# latch_THT_v2.net
KiCad netlist of a schematic drawn in EAGLE
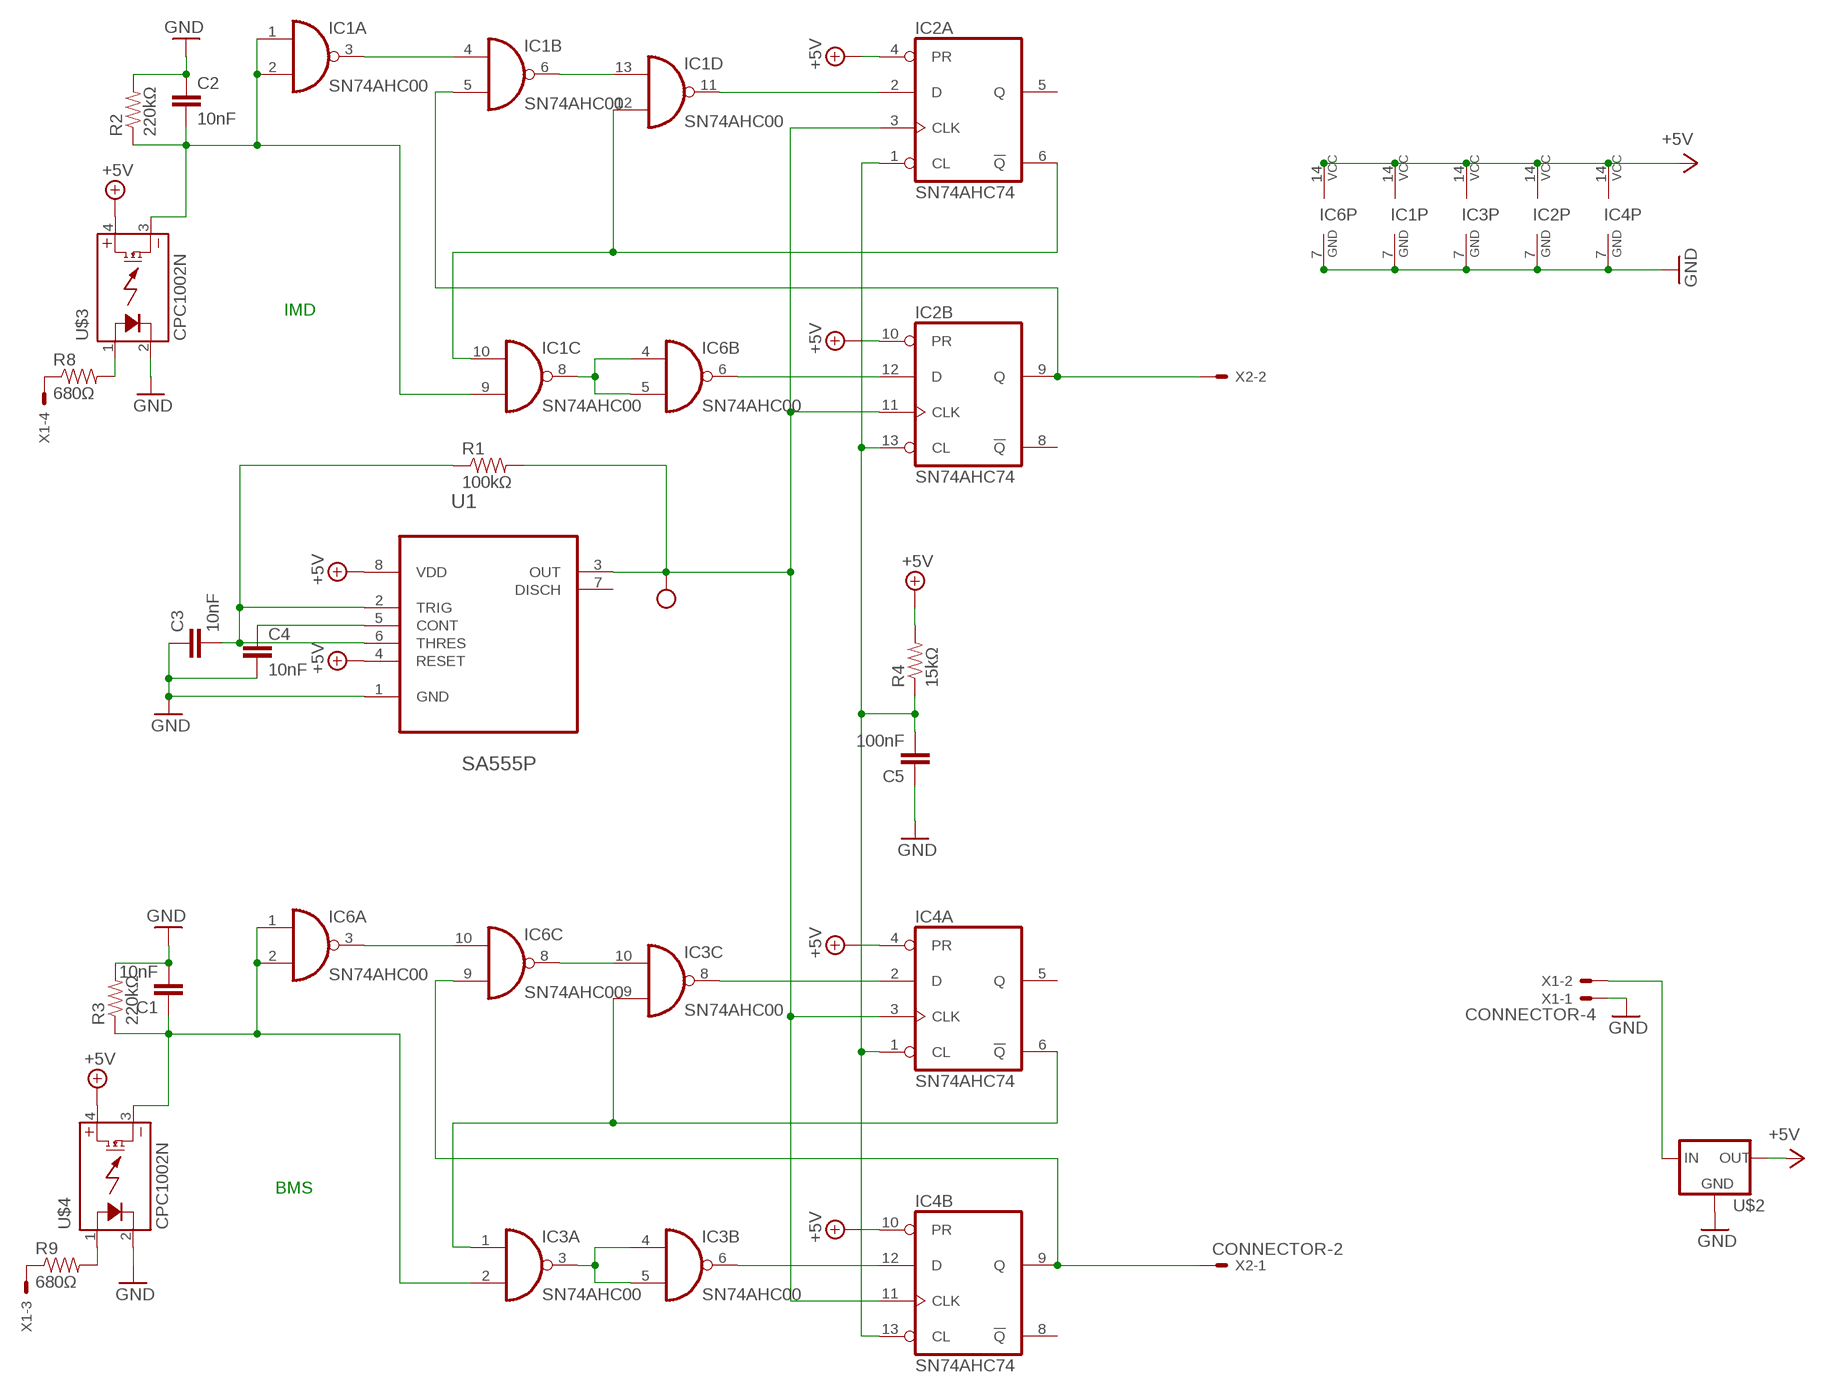
[diagram p0: schematic, sheet 1]

(export (version "E")
  (design (tool "Eeschema 10.0.6"))
  (components
    (comp (ref "C1")
      (value "10nF")
      (footprint "eagle-import:AXIAL-5MM")
      (libsource (lib "eagle-import") (part "CAP_"))
    )
    (comp (ref "C2")
      (value "10nF")
      (footprint "eagle-import:AXIAL-5MM")
      (libsource (lib "eagle-import") (part "CAP_"))
    )
    (comp (ref "C3")
      (value "10nF")
      (footprint "eagle-import:AXIAL-5MM")
      (libsource (lib "eagle-import") (part "CAP_"))
    )
    (comp (ref "C4")
      (value "10nF")
      (footprint "eagle-import:AXIAL-5MM")
      (libsource (lib "eagle-import") (part "CAP_"))
    )
    (comp (ref "C5")
      (value "100nF")
      (footprint "eagle-import:AXIAL-5MM")
      (libsource (lib "eagle-import") (part "CAP_"))
    )
    (comp (ref "IC1")
      (value "SN74AHC00")
      (footprint "eagle-import:DIL14")
      (libsource (lib "eagle-import") (part "SN74AHC00"))
    )
    (comp (ref "IC2")
      (value "SN74AHC74")
      (footprint "eagle-import:DIL14")
      (libsource (lib "eagle-import") (part "SN74AHC74"))
    )
    (comp (ref "IC3")
      (value "SN74AHC00")
      (footprint "eagle-import:DIL14")
      (libsource (lib "eagle-import") (part "SN74AHC00"))
    )
    (comp (ref "IC4")
      (value "SN74AHC74")
      (footprint "eagle-import:DIL14")
      (libsource (lib "eagle-import") (part "SN74AHC74"))
    )
    (comp (ref "IC6")
      (value "SN74AHC00")
      (footprint "eagle-import:DIL14")
      (libsource (lib "eagle-import") (part "SN74AHC00"))
    )
    (comp (ref "R1")
      (value "100kΩ")
      (footprint "eagle-import:AXIAL-0.4")
      (libsource (lib "eagle-import") (part "RESISTORPTH-1/4W"))
    )
    (comp (ref "R2")
      (value "220kΩ")
      (footprint "eagle-import:AXIAL-0.4")
      (libsource (lib "eagle-import") (part "RESISTORPTH-1/4W"))
    )
    (comp (ref "R3")
      (value "220kΩ")
      (footprint "eagle-import:AXIAL-0.4")
      (libsource (lib "eagle-import") (part "RESISTORPTH-1/4W"))
    )
    (comp (ref "R4")
      (value "15kΩ")
      (footprint "eagle-import:AXIAL-0.4")
      (libsource (lib "eagle-import") (part "RESISTORPTH-1/4W"))
    )
    (comp (ref "R8")
      (value "680Ω")
      (footprint "eagle-import:AXIAL-0.4")
      (libsource (lib "eagle-import") (part "RESISTORPTH-1/4W"))
    )
    (comp (ref "R9")
      (value "680Ω")
      (footprint "eagle-import:AXIAL-0.4")
      (libsource (lib "eagle-import") (part "RESISTORPTH-1/4W"))
    )
    (comp (ref "U$1")
      (value "TEST_POINT")
      (footprint "eagle-import:TEST_POINT")
      (libsource (lib "eagle-import") (part "TEST_POINT"))
    )
    (comp (ref "U$2")
      (value "5VREG_LM340-NLM340T-5.0/NOPB")
      (footprint "eagle-import:TO-220")
      (libsource (lib "eagle-import") (part "5VREG_LM340-NLM340T-5.0/NOPB"))
    )
    (comp (ref "U$3")
      (value "CPC1002N")
      (footprint "eagle-import:SOP04")
      (libsource (lib "eagle-import") (part "CPC1002N"))
    )
    (comp (ref "U$4")
      (value "CPC1002N")
      (footprint "eagle-import:SOP04")
      (libsource (lib "eagle-import") (part "CPC1002N"))
    )
    (comp (ref "U1")
      (value "SA555P")
      (footprint "eagle-import:DIP254P762X508-8")
      (libsource (lib "eagle-import") (part "SA555P"))
    )
    (comp (ref "X1")
      (value "CONNECTOR-4")
      (footprint "eagle-import:MINIFIT_5566-4")
      (libsource (lib "eagle-import") (part "CONNECTOR-4"))
    )
    (comp (ref "X2")
      (value "CONNECTOR-2")
      (footprint "eagle-import:MINIFIT_5566-2")
      (libsource (lib "eagle-import") (part "CONNECTOR-2"))
    )
  )
  (nets
    (net (code "1") (name "+5V") (class "Default")
      (node (ref "IC1") (pin "14") (pinfunction "VCC_14") (pintype "power_in"))
      (node (ref "IC2") (pin "10") (pinfunction "PR_10") (pintype "input"))
      (node (ref "IC2") (pin "14") (pinfunction "VCC_14") (pintype "power_in"))
      (node (ref "IC2") (pin "4") (pinfunction "PR_4") (pintype "input"))
      (node (ref "IC3") (pin "14") (pinfunction "VCC_14") (pintype "power_in"))
      (node (ref "IC4") (pin "10") (pinfunction "PR_10") (pintype "input"))
      (node (ref "IC4") (pin "14") (pinfunction "VCC_14") (pintype "power_in"))
      (node (ref "IC4") (pin "4") (pinfunction "PR_4") (pintype "input"))
      (node (ref "IC6") (pin "14") (pinfunction "VCC_14") (pintype "power_in"))
      (node (ref "R4") (pin "P$2") (pinfunction "2_P$2") (pintype "passive"))
      (node (ref "U$2") (pin "3") (pinfunction "OUT_3") (pintype "output"))
      (node (ref "U$3") (pin "4") (pinfunction "DC+_4") (pintype "passive"))
      (node (ref "U$4") (pin "4") (pinfunction "DC+_4") (pintype "passive"))
      (node (ref "U1") (pin "4") (pinfunction "RESET_4") (pintype "input"))
      (node (ref "U1") (pin "8") (pinfunction "VDD_8") (pintype "power_in"))
    )
    (net (code "2") (name "GND") (class "Default")
      (node (ref "C1") (pin "P$2") (pinfunction "2_P$2") (pintype "passive"))
      (node (ref "C2") (pin "P$1") (pinfunction "1_P$1") (pintype "passive"))
      (node (ref "C3") (pin "P$1") (pinfunction "1_P$1") (pintype "passive"))
      (node (ref "C4") (pin "P$2") (pinfunction "2_P$2") (pintype "passive"))
      (node (ref "C5") (pin "P$1") (pinfunction "1_P$1") (pintype "passive"))
      (node (ref "IC1") (pin "7") (pinfunction "GND_7") (pintype "power_in"))
      (node (ref "IC2") (pin "7") (pinfunction "GND_7") (pintype "power_in"))
      (node (ref "IC3") (pin "7") (pinfunction "GND_7") (pintype "power_in"))
      (node (ref "IC4") (pin "7") (pinfunction "GND_7") (pintype "power_in"))
      (node (ref "IC6") (pin "7") (pinfunction "GND_7") (pintype "power_in"))
      (node (ref "R2") (pin "P$2") (pinfunction "2_P$2") (pintype "passive"))
      (node (ref "R3") (pin "P$2") (pinfunction "2_P$2") (pintype "passive"))
      (node (ref "U$2") (pin "2") (pinfunction "GND_2") (pintype "input"))
      (node (ref "U$3") (pin "2") (pinfunction "CONTROL-_2") (pintype "passive"))
      (node (ref "U$4") (pin "2") (pinfunction "CONTROL-_2") (pintype "passive"))
      (node (ref "U1") (pin "1") (pinfunction "GND_1") (pintype "passive"))
      (node (ref "X1") (pin "1") (pinfunction "S_1") (pintype "passive"))
    )
    (net (code "3") (name "Net-(C1-1)") (class "Default")
      (node (ref "C1") (pin "P$1") (pinfunction "1_P$1") (pintype "passive"))
      (node (ref "IC3") (pin "2") (pinfunction "I1_2") (pintype "input"))
      (node (ref "IC6") (pin "1") (pinfunction "I0_1") (pintype "input"))
      (node (ref "IC6") (pin "2") (pinfunction "I1_2") (pintype "input"))
      (node (ref "R3") (pin "P$1") (pinfunction "1_P$1") (pintype "passive"))
      (node (ref "U$4") (pin "3") (pinfunction "DC-_3") (pintype "passive"))
    )
    (net (code "4") (name "Net-(C2-2)") (class "Default")
      (node (ref "C2") (pin "P$2") (pinfunction "2_P$2") (pintype "passive"))
      (node (ref "IC1") (pin "1") (pinfunction "I0_1") (pintype "input"))
      (node (ref "IC1") (pin "2") (pinfunction "I1_2") (pintype "input"))
      (node (ref "IC1") (pin "9") (pinfunction "I1_9") (pintype "input"))
      (node (ref "R2") (pin "P$1") (pinfunction "1_P$1") (pintype "passive"))
      (node (ref "U$3") (pin "3") (pinfunction "DC-_3") (pintype "passive"))
    )
    (net (code "5") (name "Net-(C3-2)") (class "Default")
      (node (ref "C3") (pin "P$2") (pinfunction "2_P$2") (pintype "passive"))
      (node (ref "R1") (pin "P$1") (pinfunction "1_P$1") (pintype "passive"))
      (node (ref "U1") (pin "2") (pinfunction "TRIG_2") (pintype "input"))
      (node (ref "U1") (pin "6") (pinfunction "THRES_6") (pintype "input"))
    )
    (net (code "6") (name "Net-(C4-1)") (class "Default")
      (node (ref "C4") (pin "P$1") (pinfunction "1_P$1") (pintype "passive"))
      (node (ref "U1") (pin "5") (pinfunction "CONT_5") (pintype "input"))
    )
    (net (code "7") (name "Net-(C5-2)") (class "Default")
      (node (ref "C5") (pin "P$2") (pinfunction "2_P$2") (pintype "passive"))
      (node (ref "IC2") (pin "1") (pinfunction "CL_1") (pintype "input"))
      (node (ref "IC2") (pin "13") (pinfunction "CL_13") (pintype "input"))
      (node (ref "IC4") (pin "1") (pinfunction "CL_1") (pintype "input"))
      (node (ref "IC4") (pin "13") (pinfunction "CL_13") (pintype "input"))
      (node (ref "R4") (pin "P$1") (pinfunction "1_P$1") (pintype "passive"))
    )
    (net (code "8") (name "Net-(IC1A-O)") (class "Default")
      (node (ref "IC1") (pin "3") (pinfunction "O_3") (pintype "output"))
      (node (ref "IC1") (pin "4") (pinfunction "I0_4") (pintype "input"))
    )
    (net (code "9") (name "Net-(IC1B-I1)") (class "Default")
      (node (ref "IC1") (pin "5") (pinfunction "I1_5") (pintype "input"))
      (node (ref "IC2") (pin "9") (pinfunction "Q_9") (pintype "output"))
      (node (ref "X2") (pin "2") (pinfunction "S_2") (pintype "passive"))
    )
    (net (code "10") (name "Net-(IC1B-O)") (class "Default")
      (node (ref "IC1") (pin "13") (pinfunction "I0_13") (pintype "input"))
      (node (ref "IC1") (pin "6") (pinfunction "O_6") (pintype "output"))
    )
    (net (code "11") (name "Net-(IC1C-I0)") (class "Default")
      (node (ref "IC1") (pin "10") (pinfunction "I0_10") (pintype "input"))
      (node (ref "IC1") (pin "12") (pinfunction "I1_12") (pintype "input"))
      (node (ref "IC2") (pin "6") (pinfunction "~{Q}_6") (pintype "output"))
    )
    (net (code "12") (name "Net-(IC1C-O)") (class "Default")
      (node (ref "IC1") (pin "8") (pinfunction "O_8") (pintype "output"))
      (node (ref "IC6") (pin "4") (pinfunction "I0_4") (pintype "input"))
      (node (ref "IC6") (pin "5") (pinfunction "I1_5") (pintype "input"))
    )
    (net (code "13") (name "Net-(IC1D-O)") (class "Default")
      (node (ref "IC1") (pin "11") (pinfunction "O_11") (pintype "output"))
      (node (ref "IC2") (pin "2") (pinfunction "D_2") (pintype "input"))
    )
    (net (code "14") (name "Net-(IC2A-CLK)") (class "Default")
      (node (ref "IC2") (pin "11") (pinfunction "CLK_11") (pintype "input"))
      (node (ref "IC2") (pin "3") (pinfunction "CLK_3") (pintype "input"))
      (node (ref "IC4") (pin "11") (pinfunction "CLK_11") (pintype "input"))
      (node (ref "IC4") (pin "3") (pinfunction "CLK_3") (pintype "input"))
      (node (ref "R1") (pin "P$2") (pinfunction "2_P$2") (pintype "passive"))
      (node (ref "U$1") (pin "P$1") (pinfunction "P$1_P$1") (pintype "bidirectional"))
      (node (ref "U1") (pin "3") (pinfunction "OUT_3") (pintype "output"))
    )
    (net (code "15") (name "Net-(IC2B-D)") (class "Default")
      (node (ref "IC2") (pin "12") (pinfunction "D_12") (pintype "input"))
      (node (ref "IC6") (pin "6") (pinfunction "O_6") (pintype "output"))
    )
    (net (code "16") (name "Net-(IC3A-I0)") (class "Default")
      (node (ref "IC3") (pin "1") (pinfunction "I0_1") (pintype "input"))
      (node (ref "IC3") (pin "9") (pinfunction "I1_9") (pintype "input"))
      (node (ref "IC4") (pin "6") (pinfunction "~{Q}_6") (pintype "output"))
    )
    (net (code "17") (name "Net-(IC3A-O)") (class "Default")
      (node (ref "IC3") (pin "3") (pinfunction "O_3") (pintype "output"))
      (node (ref "IC3") (pin "4") (pinfunction "I0_4") (pintype "input"))
      (node (ref "IC3") (pin "5") (pinfunction "I1_5") (pintype "input"))
    )
    (net (code "18") (name "Net-(IC3B-O)") (class "Default")
      (node (ref "IC3") (pin "6") (pinfunction "O_6") (pintype "output"))
      (node (ref "IC4") (pin "12") (pinfunction "D_12") (pintype "input"))
    )
    (net (code "19") (name "Net-(IC3C-I0)") (class "Default")
      (node (ref "IC3") (pin "10") (pinfunction "I0_10") (pintype "input"))
      (node (ref "IC6") (pin "8") (pinfunction "O_8") (pintype "output"))
    )
    (net (code "20") (name "Net-(IC3C-O)") (class "Default")
      (node (ref "IC3") (pin "8") (pinfunction "O_8") (pintype "output"))
      (node (ref "IC4") (pin "2") (pinfunction "D_2") (pintype "input"))
    )
    (net (code "21") (name "Net-(IC4B-Q)") (class "Default")
      (node (ref "IC4") (pin "9") (pinfunction "Q_9") (pintype "output"))
      (node (ref "IC6") (pin "9") (pinfunction "I1_9") (pintype "input"))
      (node (ref "X2") (pin "1") (pinfunction "S_1") (pintype "passive"))
    )
    (net (code "22") (name "Net-(IC6A-O)") (class "Default")
      (node (ref "IC6") (pin "10") (pinfunction "I0_10") (pintype "input"))
      (node (ref "IC6") (pin "3") (pinfunction "O_3") (pintype "output"))
    )
    (net (code "23") (name "Net-(R8-1)") (class "Default")
      (node (ref "R8") (pin "P$1") (pinfunction "1_P$1") (pintype "passive"))
      (node (ref "X1") (pin "4") (pinfunction "S_4") (pintype "passive"))
    )
    (net (code "24") (name "Net-(R8-2)") (class "Default")
      (node (ref "R8") (pin "P$2") (pinfunction "2_P$2") (pintype "passive"))
      (node (ref "U$3") (pin "1") (pinfunction "CONTROL+_1") (pintype "passive"))
    )
    (net (code "25") (name "Net-(R9-1)") (class "Default")
      (node (ref "R9") (pin "P$1") (pinfunction "1_P$1") (pintype "passive"))
      (node (ref "X1") (pin "3") (pinfunction "S_3") (pintype "passive"))
    )
    (net (code "26") (name "Net-(R9-2)") (class "Default")
      (node (ref "R9") (pin "P$2") (pinfunction "2_P$2") (pintype "passive"))
      (node (ref "U$4") (pin "1") (pinfunction "CONTROL+_1") (pintype "passive"))
    )
    (net (code "27") (name "Net-(U$2-IN)") (class "Default")
      (node (ref "U$2") (pin "1") (pinfunction "IN_1") (pintype "input"))
      (node (ref "X1") (pin "2") (pinfunction "S_2") (pintype "passive"))
    )
    (net (code "28") (name "unconnected-(IC2A-Q-Pad5)") (class "Default")
      (node (ref "IC2") (pin "5") (pinfunction "Q_5") (pintype "output"))
    )
    (net (code "29") (name "unconnected-(IC2B-~{Q}-Pad8)") (class "Default")
      (node (ref "IC2") (pin "8") (pinfunction "~{Q}_8") (pintype "output"))
    )
    (net (code "30") (name "unconnected-(IC4A-Q-Pad5)") (class "Default")
      (node (ref "IC4") (pin "5") (pinfunction "Q_5") (pintype "output"))
    )
    (net (code "31") (name "unconnected-(IC4B-~{Q}-Pad8)") (class "Default")
      (node (ref "IC4") (pin "8") (pinfunction "~{Q}_8") (pintype "output"))
    )
    (net (code "32") (name "unconnected-(U1-DISCH-Pad7)") (class "Default")
      (node (ref "U1") (pin "7") (pinfunction "DISCH_7") (pintype "output"))
    )
  )
)
